# Trolly.net
KiCad netlist of a schematic drawn in EAGLE
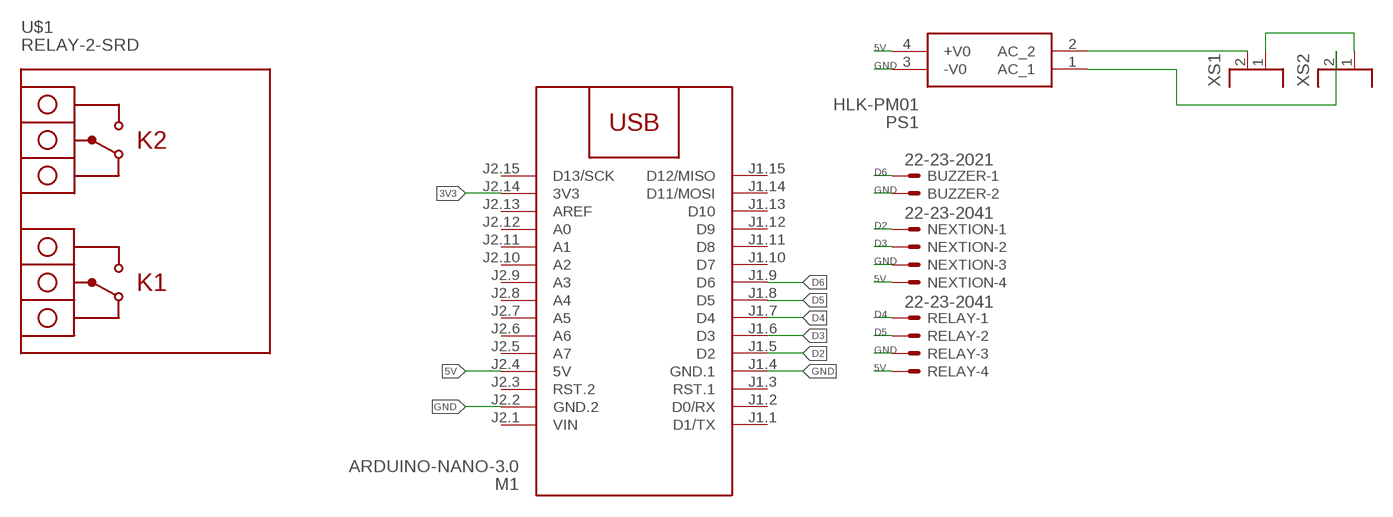
[diagram p0: schematic, sheet 1]

(export (version "E")
  (design (tool "Eeschema 10.0.6"))
  (components
    (comp (ref "BUZZER")
      (value "22-23-2021")
      (footprint "eagle-import:22-23-2021")
      (fields (field (name "MF") "MOLEX"))
      (libsource (lib "eagle-import") (part "22-23-2021"))
    )
    (comp (ref "M1")
      (value "ARDUINO-NANO-3.0")
      (footprint "eagle-import:ARDUINO-NANO-3.0")
      (libsource (lib "eagle-import") (part "ARDUINO-NANO-3.0"))
    )
    (comp (ref "NEXTION")
      (value "22-23-2041")
      (footprint "eagle-import:22-23-2041")
      (fields (field (name "MF") "MOLEX"))
      (libsource (lib "eagle-import") (part "22-23-2041"))
    )
    (comp (ref "PS1")
      (value "HLK-PM01")
      (footprint "eagle-import:HLKPM01")
      (fields (field (name "MF") "Hi-link") (field (name "MP") "hlk-pm01"))
      (libsource (lib "eagle-import") (part "HLK-PM01"))
    )
    (comp (ref "RELAY")
      (value "22-23-2041")
      (footprint "eagle-import:22-23-2041")
      (fields (field (name "MF") "MOLEX"))
      (libsource (lib "eagle-import") (part "22-23-2041"))
    )
    (comp (ref "U$1")
      (value "RELAY-2-SRD")
      (footprint "eagle-import:RELAY-2-SRD")
      (libsource (lib "eagle-import") (part "RELAY-2-SRD"))
    )
    (comp (ref "XS1")
      (value "2P")
      (footprint "eagle-import:DG55CB-2P-1")
      (libsource (lib "eagle-import") (part "2P"))
    )
    (comp (ref "XS2")
      (value "2P")
      (footprint "eagle-import:DG55CB-2P-1")
      (libsource (lib "eagle-import") (part "2P"))
    )
  )
  (nets
    (net (code "1") (name "/VIN") (class "Default")
      (node (ref "M1") (pin "J2.1") (pinfunction "VIN_J2.1") (pintype "power_in"))
    )
    (net (code "2") (name "3V3") (class "Default")
      (node (ref "M1") (pin "J2.14") (pinfunction "3V3_J2.14") (pintype "power_in"))
    )
    (net (code "3") (name "5V") (class "Default")
      (node (ref "M1") (pin "J2.4") (pinfunction "5V_J2.4") (pintype "power_in"))
      (node (ref "NEXTION") (pin "4") (pinfunction "S_4") (pintype "passive"))
      (node (ref "PS1") (pin "4") (pinfunction "+V0_4") (pintype "bidirectional"))
      (node (ref "RELAY") (pin "4") (pinfunction "S_4") (pintype "passive"))
    )
    (net (code "4") (name "D2") (class "Default")
      (node (ref "M1") (pin "J1.5") (pinfunction "D2_J1.5") (pintype "bidirectional"))
      (node (ref "NEXTION") (pin "1") (pinfunction "S_1") (pintype "passive"))
    )
    (net (code "5") (name "D3") (class "Default")
      (node (ref "M1") (pin "J1.6") (pinfunction "D3_J1.6") (pintype "bidirectional"))
      (node (ref "NEXTION") (pin "2") (pinfunction "S_2") (pintype "passive"))
    )
    (net (code "6") (name "D4") (class "Default")
      (node (ref "M1") (pin "J1.7") (pinfunction "D4_J1.7") (pintype "bidirectional"))
      (node (ref "RELAY") (pin "1") (pinfunction "S_1") (pintype "passive"))
    )
    (net (code "7") (name "D5") (class "Default")
      (node (ref "M1") (pin "J1.8") (pinfunction "D5_J1.8") (pintype "bidirectional"))
      (node (ref "RELAY") (pin "2") (pinfunction "S_2") (pintype "passive"))
    )
    (net (code "8") (name "D6") (class "Default")
      (node (ref "BUZZER") (pin "1") (pinfunction "S_1") (pintype "passive"))
      (node (ref "M1") (pin "J1.9") (pinfunction "D6_J1.9") (pintype "bidirectional"))
    )
    (net (code "9") (name "GND") (class "Default")
      (node (ref "BUZZER") (pin "2") (pinfunction "S_2") (pintype "passive"))
      (node (ref "M1") (pin "J1.4") (pinfunction "GND.1_J1.4") (pintype "power_in"))
      (node (ref "M1") (pin "J2.2") (pinfunction "GND.2_J2.2") (pintype "power_in"))
      (node (ref "NEXTION") (pin "3") (pinfunction "S_3") (pintype "passive"))
      (node (ref "PS1") (pin "3") (pinfunction "-V0_3") (pintype "bidirectional"))
      (node (ref "RELAY") (pin "3") (pinfunction "S_3") (pintype "passive"))
    )
    (net (code "10") (name "Net-(PS1-AC_1)") (class "Default")
      (node (ref "PS1") (pin "1") (pinfunction "AC_1_1") (pintype "bidirectional"))
      (node (ref "XS2") (pin "2") (pinfunction "P$2_2") (pintype "bidirectional"))
    )
    (net (code "11") (name "Net-(PS1-AC_2)") (class "Default")
      (node (ref "PS1") (pin "2") (pinfunction "AC_2_2") (pintype "bidirectional"))
      (node (ref "XS1") (pin "2") (pinfunction "P$2_2") (pintype "bidirectional"))
    )
    (net (code "12") (name "Net-(XS1-P$1)") (class "Default")
      (node (ref "XS1") (pin "1") (pinfunction "P$1_1") (pintype "bidirectional"))
      (node (ref "XS2") (pin "1") (pinfunction "P$1_1") (pintype "bidirectional"))
    )
    (net (code "13") (name "unconnected-(M1-A0-PadJ2.12)") (class "Default")
      (node (ref "M1") (pin "J2.12") (pinfunction "A0_J2.12") (pintype "bidirectional"))
    )
    (net (code "14") (name "unconnected-(M1-A1-PadJ2.11)") (class "Default")
      (node (ref "M1") (pin "J2.11") (pinfunction "A1_J2.11") (pintype "bidirectional"))
    )
    (net (code "15") (name "unconnected-(M1-A2-PadJ2.10)") (class "Default")
      (node (ref "M1") (pin "J2.10") (pinfunction "A2_J2.10") (pintype "bidirectional"))
    )
    (net (code "16") (name "unconnected-(M1-A3-PadJ2.9)") (class "Default")
      (node (ref "M1") (pin "J2.9") (pinfunction "A3_J2.9") (pintype "bidirectional"))
    )
    (net (code "17") (name "unconnected-(M1-A4-PadJ2.8)") (class "Default")
      (node (ref "M1") (pin "J2.8") (pinfunction "A4_J2.8") (pintype "bidirectional"))
    )
    (net (code "18") (name "unconnected-(M1-A5-PadJ2.7)") (class "Default")
      (node (ref "M1") (pin "J2.7") (pinfunction "A5_J2.7") (pintype "bidirectional"))
    )
    (net (code "19") (name "unconnected-(M1-A6-PadJ2.6)") (class "Default")
      (node (ref "M1") (pin "J2.6") (pinfunction "A6_J2.6") (pintype "bidirectional"))
    )
    (net (code "20") (name "unconnected-(M1-A7-PadJ2.5)") (class "Default")
      (node (ref "M1") (pin "J2.5") (pinfunction "A7_J2.5") (pintype "bidirectional"))
    )
    (net (code "21") (name "unconnected-(M1-AREF-PadJ2.13)") (class "Default")
      (node (ref "M1") (pin "J2.13") (pinfunction "AREF_J2.13") (pintype "bidirectional"))
    )
    (net (code "22") (name "unconnected-(M1-D0{slash}RX-PadJ1.2)") (class "Default")
      (node (ref "M1") (pin "J1.2") (pinfunction "D0/RX_J1.2") (pintype "bidirectional"))
    )
    (net (code "23") (name "unconnected-(M1-D1{slash}TX-PadJ1.1)") (class "Default")
      (node (ref "M1") (pin "J1.1") (pinfunction "D1/TX_J1.1") (pintype "bidirectional"))
    )
    (net (code "24") (name "unconnected-(M1-D7-PadJ1.10)") (class "Default")
      (node (ref "M1") (pin "J1.10") (pinfunction "D7_J1.10") (pintype "bidirectional"))
    )
    (net (code "25") (name "unconnected-(M1-D8-PadJ1.11)") (class "Default")
      (node (ref "M1") (pin "J1.11") (pinfunction "D8_J1.11") (pintype "bidirectional"))
    )
    (net (code "26") (name "unconnected-(M1-D9-PadJ1.12)") (class "Default")
      (node (ref "M1") (pin "J1.12") (pinfunction "D9_J1.12") (pintype "bidirectional"))
    )
    (net (code "27") (name "unconnected-(M1-D10-PadJ1.13)") (class "Default")
      (node (ref "M1") (pin "J1.13") (pinfunction "D10_J1.13") (pintype "bidirectional"))
    )
    (net (code "28") (name "unconnected-(M1-D11{slash}MOSI-PadJ1.14)") (class "Default")
      (node (ref "M1") (pin "J1.14") (pinfunction "D11/MOSI_J1.14") (pintype "bidirectional"))
    )
    (net (code "29") (name "unconnected-(M1-D12{slash}MISO-PadJ1.15)") (class "Default")
      (node (ref "M1") (pin "J1.15") (pinfunction "D12/MISO_J1.15") (pintype "bidirectional"))
    )
    (net (code "30") (name "unconnected-(M1-D13{slash}SCK-PadJ2.15)") (class "Default")
      (node (ref "M1") (pin "J2.15") (pinfunction "D13/SCK_J2.15") (pintype "bidirectional"))
    )
    (net (code "31") (name "unconnected-(M1-RST.1-PadJ1.3)") (class "Default")
      (node (ref "M1") (pin "J1.3") (pinfunction "RST.1_J1.3") (pintype "bidirectional"))
    )
    (net (code "32") (name "unconnected-(M1-RST.2-PadJ2.3)") (class "Default")
      (node (ref "M1") (pin "J2.3") (pinfunction "RST.2_J2.3") (pintype "bidirectional"))
    )
  )
)
